# AT89S52.net
KiCad netlist of a schematic drawn in Altium Designer
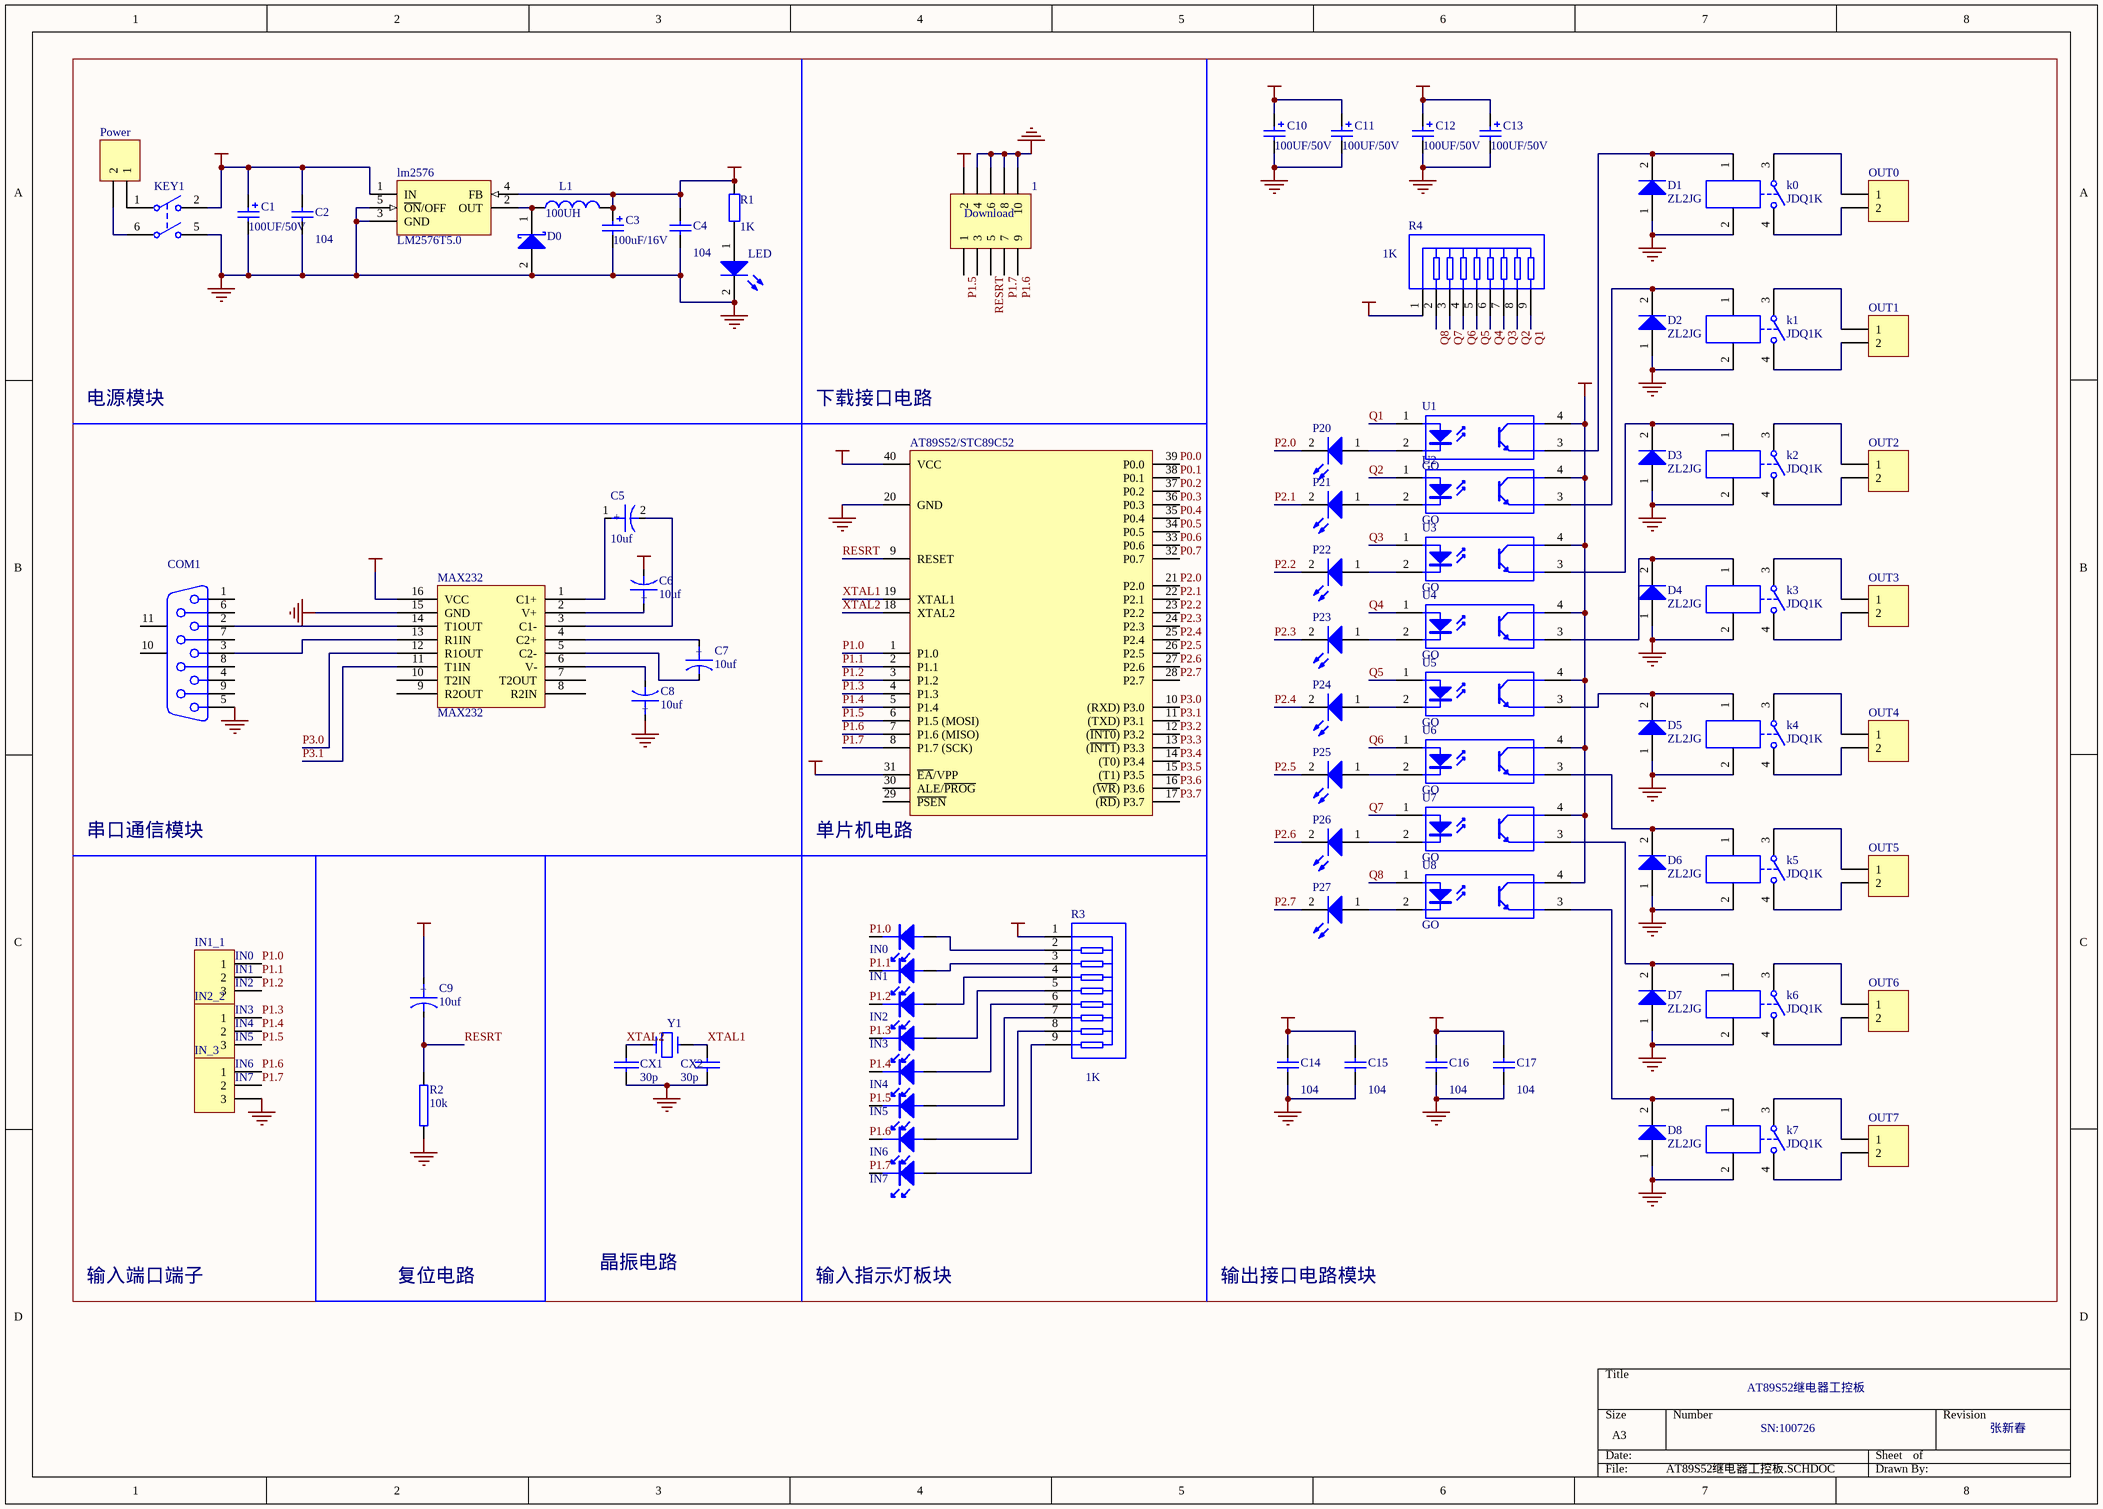
[diagram p0: AT89S52继电器工控板.SCHDOC]

(export (version "E")
  (design (tool "Eeschema 10.0.6"))
  (components
    (comp (ref "1")
      (value "Download")
      (footprint "HDR-2x5")
      (description "Header, 5-Pin, Dual row")
      (fields (field (name "PUBLISHER") "Altium Limited"))
      (libsource (lib "Miscellaneous Connectors") (part "Header 5X2"))
    )
    (comp (ref "AT89S52/STC89C52")
      (value "~")
      (footprint "DIP-40")
      (description "8 位微处理器/40引脚")
      (fields (field (name "发布者") "磊元工作室"))
      (libsource (lib "MCU") (part "AT89S52-P"))
    )
    (comp (ref "C1")
      (value "100UF/50V")
      (footprint "C-DJ-6")
      (description "电解电容")
      (fields (field (name "Comment") "DJDR") (field (name "PUBLISHER") "Altium Limited"))
      (libsource (lib "zxcourhc") (part "DJDR"))
    )
    (comp (ref "C2")
      (value "104")
      (footprint "CPDR")
      (description "瓷片电容")
      (fields (field (name "Comment") "CPDR") (field (name "PUBLISHER") "Altium Limited"))
      (libsource (lib "zxcourhc") (part "CPDR"))
    )
    (comp (ref "C3")
      (value "100uF/16V")
      (footprint "C-DJ-6")
      (description "电解电容")
      (fields (field (name "Comment") "DJDR") (field (name "PUBLISHER") "Altium Limited"))
      (libsource (lib "zxcourhc") (part "DJDR"))
    )
    (comp (ref "C4")
      (value "104")
      (footprint "CPDR")
      (description "瓷片电容")
      (fields (field (name "Comment") "CPDR") (field (name "PUBLISHER") "Altium Limited"))
      (libsource (lib "zxcourhc") (part "CPDR"))
    )
    (comp (ref "C5")
      (value "10uf")
      (footprint "C-DJ-4")
      (description "Capacitor")
      (libsource (lib "") (part "CAPACITOR POL_1"))
    )
    (comp (ref "C6")
      (value "10uf")
      (footprint "C-DJ-4")
      (description "Capacitor")
      (libsource (lib "*") (part "CAPACITOR POL"))
    )
    (comp (ref "C7")
      (value "10uf")
      (footprint "C-DJ-4")
      (description "Capacitor")
      (libsource (lib "*") (part "CAPACITOR POL"))
    )
    (comp (ref "C8")
      (value "10uf")
      (footprint "C-DJ-4")
      (description "Capacitor")
      (libsource (lib "*") (part "CAPACITOR POL"))
    )
    (comp (ref "C9")
      (value "10uf")
      (footprint "C-DJ-4")
      (description "Capacitor")
      (libsource (lib "*") (part "CAPACITOR POL"))
    )
    (comp (ref "C10")
      (value "100UF/50V")
      (footprint "C-DJ-6")
      (description "电解电容")
      (fields (field (name "Comment") "DJDR") (field (name "PUBLISHER") "Altium Limited"))
      (libsource (lib "zxcourhc") (part "DJDR"))
    )
    (comp (ref "C11")
      (value "100UF/50V")
      (footprint "C-DJ-6")
      (description "电解电容")
      (fields (field (name "Comment") "DJDR") (field (name "PUBLISHER") "Altium Limited"))
      (libsource (lib "zxcourhc") (part "DJDR"))
    )
    (comp (ref "C12")
      (value "100UF/50V")
      (footprint "C-DJ-6")
      (description "电解电容")
      (fields (field (name "Comment") "DJDR") (field (name "PUBLISHER") "Altium Limited"))
      (libsource (lib "zxcourhc") (part "DJDR"))
    )
    (comp (ref "C13")
      (value "100UF/50V")
      (footprint "C-DJ-6")
      (description "电解电容")
      (fields (field (name "Comment") "DJDR") (field (name "PUBLISHER") "Altium Limited"))
      (libsource (lib "zxcourhc") (part "DJDR"))
    )
    (comp (ref "C14")
      (value "104")
      (footprint "CPDR")
      (description "瓷片电容")
      (fields (field (name "Comment") "CPDR") (field (name "PUBLISHER") "Altium Limited"))
      (libsource (lib "zxcourhc") (part "CPDR"))
    )
    (comp (ref "C15")
      (value "104")
      (footprint "CPDR")
      (description "瓷片电容")
      (fields (field (name "Comment") "CPDR") (field (name "PUBLISHER") "Altium Limited"))
      (libsource (lib "zxcourhc") (part "CPDR"))
    )
    (comp (ref "C16")
      (value "104")
      (footprint "CPDR")
      (description "瓷片电容")
      (fields (field (name "Comment") "CPDR") (field (name "PUBLISHER") "Altium Limited"))
      (libsource (lib "zxcourhc") (part "CPDR"))
    )
    (comp (ref "C17")
      (value "104")
      (footprint "CPDR")
      (description "瓷片电容")
      (fields (field (name "Comment") "CPDR") (field (name "PUBLISHER") "Altium Limited"))
      (libsource (lib "zxcourhc") (part "CPDR"))
    )
    (comp (ref "COM1")
      (value "D Connector 9")
      (footprint "DSUB1.385-2H9")
      (description "Receptacle Assembly, 9 Position, Right Angle")
      (fields (field (name "PUBLISHER") "Altium Limited"))
      (libsource (lib "Miscellaneous Connectors") (part "D Connector 9"))
    )
    (comp (ref "CX1")
      (value "30p")
      (footprint "HDR1X2")
      (description "Capacitor")
      (libsource (lib "*") (part "CAP"))
    )
    (comp (ref "CX2")
      (value "30p")
      (footprint "HDR1X2")
      (description "Capacitor")
      (libsource (lib "*") (part "CAP"))
    )
    (comp (ref "D0")
      (value "WY2JG")
      (footprint "ZCDZL")
      (description "稳压二级管")
      (fields (field (name "PUBLISHER") "Altium Limited"))
      (libsource (lib "zxcourhc") (part "WY2JG"))
    )
    (comp (ref "D1")
      (value "ZL2JG")
      (footprint "D-ZL-10")
      (description "整流二极管")
      (fields (field (name "PUBLISHER") "Altium Limited"))
      (libsource (lib "zxcourhc") (part "ZL2JG"))
    )
    (comp (ref "D2")
      (value "ZL2JG")
      (footprint "D-ZL-10")
      (description "整流二极管")
      (fields (field (name "PUBLISHER") "Altium Limited"))
      (libsource (lib "zxcourhc") (part "ZL2JG"))
    )
    (comp (ref "D3")
      (value "ZL2JG")
      (footprint "D-ZL-10")
      (description "整流二极管")
      (fields (field (name "PUBLISHER") "Altium Limited"))
      (libsource (lib "zxcourhc") (part "ZL2JG"))
    )
    (comp (ref "D4")
      (value "ZL2JG")
      (footprint "D-ZL-10")
      (description "整流二极管")
      (fields (field (name "PUBLISHER") "Altium Limited"))
      (libsource (lib "zxcourhc") (part "ZL2JG"))
    )
    (comp (ref "D5")
      (value "ZL2JG")
      (footprint "D-ZL-10")
      (description "整流二极管")
      (fields (field (name "PUBLISHER") "Altium Limited"))
      (libsource (lib "zxcourhc") (part "ZL2JG"))
    )
    (comp (ref "D6")
      (value "ZL2JG")
      (footprint "D-ZL-10")
      (description "整流二极管")
      (fields (field (name "PUBLISHER") "Altium Limited"))
      (libsource (lib "zxcourhc") (part "ZL2JG"))
    )
    (comp (ref "D7")
      (value "ZL2JG")
      (footprint "D-ZL-10")
      (description "整流二极管")
      (fields (field (name "PUBLISHER") "Altium Limited"))
      (libsource (lib "zxcourhc") (part "ZL2JG"))
    )
    (comp (ref "D8")
      (value "ZL2JG")
      (footprint "D-ZL-10")
      (description "整流二极管")
      (fields (field (name "PUBLISHER") "Altium Limited"))
      (libsource (lib "zxcourhc") (part "ZL2JG"))
    )
    (comp (ref "IN0") (value "LED") (footprint "HDR1X2") (libsource (lib "OldCow1 (1)") (part "LED")))
    (comp (ref "IN1") (value "LED") (footprint "HDR1X2") (libsource (lib "OldCow1 (1)") (part "LED")))
    (comp (ref "IN1_1")
      (value "PZ_3")
      (footprint "JK128_3")
      (description "排针——3")
      (fields (field (name "PUBLISHER") "Altium Limited"))
      (libsource (lib "zxcourhc") (part "PZ_3"))
    )
    (comp (ref "IN2") (value "LED") (footprint "HDR1X2") (libsource (lib "OldCow1 (1)") (part "LED")))
    (comp (ref "IN2_2")
      (value "PZ_3")
      (footprint "JK128_3")
      (description "排针——3")
      (fields (field (name "PUBLISHER") "Altium Limited"))
      (libsource (lib "zxcourhc") (part "PZ_3"))
    )
    (comp (ref "IN3") (value "LED") (footprint "HDR1X2") (libsource (lib "OldCow1 (1)") (part "LED")))
    (comp (ref "IN4") (value "LED") (footprint "HDR1X2") (libsource (lib "OldCow1 (1)") (part "LED")))
    (comp (ref "IN5") (value "LED") (footprint "HDR1X2") (libsource (lib "OldCow1 (1)") (part "LED")))
    (comp (ref "IN6") (value "LED") (footprint "HDR1X2") (libsource (lib "OldCow1 (1)") (part "LED")))
    (comp (ref "IN7") (value "LED") (footprint "HDR1X2") (libsource (lib "OldCow1 (1)") (part "LED")))
    (comp (ref "IN_3")
      (value "~")
      (footprint "JK128_3")
      (description "排针——3")
      (fields (field (name "PUBLISHER") "Altium Limited"))
      (libsource (lib "zxcourhc") (part "PZ_3"))
    )
    (comp (ref "k0")
      (value "JDQ1K")
      (footprint "JDQ1KI")
      (description "继电器一常开")
      (libsource (lib "zxcourhc") (part "JDQ1K"))
    )
    (comp (ref "k1")
      (value "JDQ1K")
      (footprint "JDQ1KI")
      (description "继电器一常开")
      (libsource (lib "zxcourhc") (part "JDQ1K"))
    )
    (comp (ref "k2")
      (value "JDQ1K")
      (footprint "JDQ1KI")
      (description "继电器一常开")
      (libsource (lib "zxcourhc") (part "JDQ1K"))
    )
    (comp (ref "k3")
      (value "JDQ1K")
      (footprint "JDQ1KI")
      (description "继电器一常开")
      (libsource (lib "zxcourhc") (part "JDQ1K"))
    )
    (comp (ref "k4")
      (value "JDQ1K")
      (footprint "JDQ1KI")
      (description "继电器一常开")
      (libsource (lib "zxcourhc") (part "JDQ1K"))
    )
    (comp (ref "k5")
      (value "JDQ1K")
      (footprint "JDQ1KI")
      (description "继电器一常开")
      (libsource (lib "zxcourhc") (part "JDQ1K"))
    )
    (comp (ref "k6")
      (value "JDQ1K")
      (footprint "JDQ1KI")
      (description "继电器一常开")
      (libsource (lib "zxcourhc") (part "JDQ1K"))
    )
    (comp (ref "k7")
      (value "JDQ1K")
      (footprint "JDQ1KI")
      (description "继电器一常开")
      (libsource (lib "zxcourhc") (part "JDQ1K"))
    )
    (comp (ref "KEY1")
      (value "SW-DPST")
      (footprint "DPDT-6")
      (description "Double-Pole, Single-Throw Switch")
      (fields (field (name "PUBLISHER") "Altium Limited"))
      (libsource (lib "Miscellaneous Devices") (part "SW-DPST"))
    )
    (comp (ref "L1")
      (value "100UH")
      (footprint "L_DG")
      (description "电感")
      (fields (field (name "Comment") "DG") (field (name "PUBLISHER") "Altium Limited"))
      (libsource (lib "zxcourhc") (part "DG"))
    )
    (comp (ref "LED")
      (value "LED")
      (footprint "LED_D")
      (description "发光二极管")
      (fields (field (name "PUBLISHER") "Altium Limited"))
      (libsource (lib "zxcourhc") (part "LED"))
    )
    (comp (ref "lm2576")
      (value "LM2576T5.0")
      (footprint "LM2576")
      (description "Simple Switcher 3A Step Down Voltage Regulator")
      (fields (field (name "PUBLISHER") "Altium Limited"))
      (libsource (lib "NSC Power Mgt Switching Regulator") (part "LM2576HVT-3.3"))
    )
    (comp (ref "MAX232") (value "MAX232") (footprint "DIP16") (libsource (lib "*") (part "MAX232")))
    (comp (ref "OUT0")
      (value "PZ_2")
      (footprint "DYDZ")
      (description "排针——2")
      (fields (field (name "PUBLISHER") "Altium Limited"))
      (libsource (lib "") (part "PZ_2_1"))
    )
    (comp (ref "OUT1")
      (value "PZ_2")
      (footprint "DYDZ")
      (description "排针——2")
      (fields (field (name "PUBLISHER") "Altium Limited"))
      (libsource (lib "") (part "PZ_2_1"))
    )
    (comp (ref "OUT2")
      (value "PZ_2")
      (footprint "DYDZ")
      (description "排针——2")
      (fields (field (name "PUBLISHER") "Altium Limited"))
      (libsource (lib "") (part "PZ_2_1"))
    )
    (comp (ref "OUT3")
      (value "PZ_2")
      (footprint "DYDZ")
      (description "排针——2")
      (fields (field (name "PUBLISHER") "Altium Limited"))
      (libsource (lib "") (part "PZ_2_1"))
    )
    (comp (ref "OUT4")
      (value "PZ_2")
      (footprint "DYDZ")
      (description "排针——2")
      (fields (field (name "PUBLISHER") "Altium Limited"))
      (libsource (lib "") (part "PZ_2_1"))
    )
    (comp (ref "OUT5")
      (value "PZ_2")
      (footprint "DYDZ")
      (description "排针——2")
      (fields (field (name "PUBLISHER") "Altium Limited"))
      (libsource (lib "") (part "PZ_2_1"))
    )
    (comp (ref "OUT6")
      (value "PZ_2")
      (footprint "DYDZ")
      (description "排针——2")
      (fields (field (name "PUBLISHER") "Altium Limited"))
      (libsource (lib "") (part "PZ_2_1"))
    )
    (comp (ref "OUT7")
      (value "PZ_2")
      (footprint "DYDZ")
      (description "排针——2")
      (fields (field (name "PUBLISHER") "Altium Limited"))
      (libsource (lib "") (part "PZ_2_1"))
    )
    (comp (ref "P20")
      (value "~")
      (footprint "CPDR")
      (description "发光二极管")
      (fields (field (name "PUBLISHER") "Altium Limited"))
      (libsource (lib "zxcourhc") (part "LED"))
    )
    (comp (ref "P21")
      (value "~")
      (footprint "CPDR")
      (description "发光二极管")
      (fields (field (name "PUBLISHER") "Altium Limited"))
      (libsource (lib "zxcourhc") (part "LED"))
    )
    (comp (ref "P22")
      (value "~")
      (footprint "CPDR")
      (description "发光二极管")
      (fields (field (name "PUBLISHER") "Altium Limited"))
      (libsource (lib "zxcourhc") (part "LED"))
    )
    (comp (ref "P23")
      (value "~")
      (footprint "CPDR")
      (description "发光二极管")
      (fields (field (name "PUBLISHER") "Altium Limited"))
      (libsource (lib "zxcourhc") (part "LED"))
    )
    (comp (ref "P24")
      (value "~")
      (footprint "CPDR")
      (description "发光二极管")
      (fields (field (name "PUBLISHER") "Altium Limited"))
      (libsource (lib "zxcourhc") (part "LED"))
    )
    (comp (ref "P25")
      (value "~")
      (footprint "CPDR")
      (description "发光二极管")
      (fields (field (name "PUBLISHER") "Altium Limited"))
      (libsource (lib "zxcourhc") (part "LED"))
    )
    (comp (ref "P26")
      (value "~")
      (footprint "CPDR")
      (description "发光二极管")
      (fields (field (name "PUBLISHER") "Altium Limited"))
      (libsource (lib "zxcourhc") (part "LED"))
    )
    (comp (ref "P27")
      (value "~")
      (footprint "CPDR")
      (description "发光二极管")
      (fields (field (name "PUBLISHER") "Altium Limited"))
      (libsource (lib "zxcourhc") (part "LED"))
    )
    (comp (ref "Power")
      (value "PZ_2")
      (footprint "JK128_2")
      (description "排针——2")
      (fields (field (name "PUBLISHER") "Altium Limited"))
      (libsource (lib "zxcourhc") (part "PZ_2"))
    )
    (comp (ref "R1")
      (value "1K")
      (footprint "CPDR")
      (description "电阻")
      (fields (field (name "Comment") "Res") (field (name "PUBLISHER") "Altium Limited"))
      (libsource (lib "zxcourhc") (part "Res"))
    )
    (comp (ref "R2") (value "10k") (footprint "CPDR") (libsource (lib "*") (part "RES2")))
    (comp (ref "R3")
      (value "1K")
      (footprint "HDR-9")
      (description "8位排阻")
      (fields (field (name "PUBLISHER") "Altium Limited"))
      (libsource (lib "zxcourhc") (part "Res PZ_8"))
    )
    (comp (ref "R4")
      (value "1K")
      (footprint "HDR-9")
      (description "8位排阻")
      (fields (field (name "PUBLISHER") "Altium Limited"))
      (libsource (lib "zxcourhc") (part "Res PZ_8"))
    )
    (comp (ref "U1")
      (value "GO")
      (footprint "DIP-4")
      (description "光耦")
      (fields (field (name "PUBLISHER") "Altium Limited"))
      (libsource (lib "zxcourhc") (part "GO"))
    )
    (comp (ref "U2")
      (value "GO")
      (footprint "DIP-4")
      (description "光耦")
      (fields (field (name "PUBLISHER") "Altium Limited"))
      (libsource (lib "zxcourhc") (part "GO"))
    )
    (comp (ref "U3")
      (value "GO")
      (footprint "DIP-4")
      (description "光耦")
      (fields (field (name "PUBLISHER") "Altium Limited"))
      (libsource (lib "zxcourhc") (part "GO"))
    )
    (comp (ref "U4")
      (value "GO")
      (footprint "DIP-4")
      (description "光耦")
      (fields (field (name "PUBLISHER") "Altium Limited"))
      (libsource (lib "zxcourhc") (part "GO"))
    )
    (comp (ref "U5")
      (value "GO")
      (footprint "DIP-4")
      (description "光耦")
      (fields (field (name "PUBLISHER") "Altium Limited"))
      (libsource (lib "zxcourhc") (part "GO"))
    )
    (comp (ref "U6")
      (value "GO")
      (footprint "DIP-4")
      (description "光耦")
      (fields (field (name "PUBLISHER") "Altium Limited"))
      (libsource (lib "zxcourhc") (part "GO"))
    )
    (comp (ref "U7")
      (value "GO")
      (footprint "DIP-4")
      (description "光耦")
      (fields (field (name "PUBLISHER") "Altium Limited"))
      (libsource (lib "zxcourhc") (part "GO"))
    )
    (comp (ref "U8")
      (value "GO")
      (footprint "DIP-4")
      (description "光耦")
      (fields (field (name "PUBLISHER") "Altium Limited"))
      (libsource (lib "zxcourhc") (part "GO"))
    )
    (comp (ref "Y1")
      (value "Y1")
      (footprint "JZ_ZC")
      (description "Crystal")
      (libsource (lib "*") (part "CRYSTAL"))
    )
  )
  (nets
    (net (code "1") (name "+5V") (class "Default")
      (node (ref "1") (pin "2") (pinfunction "2_2") (pintype "passive"))
      (node (ref "AT89S52/STC89C52") (pin "31") (pinfunction "~{EA}/VPP_31") (pintype "passive"))
      (node (ref "AT89S52/STC89C52") (pin "40") (pinfunction "VCC_40") (pintype "power_in"))
      (node (ref "C12") (pin "1") (pinfunction "1_1") (pintype "passive"))
      (node (ref "C13") (pin "1") (pinfunction "1_1") (pintype "passive"))
      (node (ref "C16") (pin "2") (pinfunction "2_2") (pintype "passive"))
      (node (ref "C17") (pin "2") (pinfunction "2_2") (pintype "passive"))
      (node (ref "C3") (pin "1") (pinfunction "1_1") (pintype "passive"))
      (node (ref "C4") (pin "2") (pinfunction "2_2") (pintype "passive"))
      (node (ref "C6") (pin "2") (pinfunction "2_2") (pintype "passive"))
      (node (ref "C9") (pin "1") (pinfunction "1_1") (pintype "passive"))
      (node (ref "L1") (pin "2") (pinfunction "2_2") (pintype "passive"))
      (node (ref "MAX232") (pin "16") (pinfunction "VCC_16") (pintype "passive"))
      (node (ref "R1") (pin "2") (pinfunction "2_2") (pintype "passive"))
      (node (ref "R3") (pin "1") (pinfunction "1_1") (pintype "passive"))
      (node (ref "R4") (pin "1") (pinfunction "1_1") (pintype "passive"))
      (node (ref "lm2576") (pin "4") (pinfunction "FB_4") (pintype "input"))
    )
    (net (code "2") (name "+12V") (class "Default")
      (node (ref "C1") (pin "1") (pinfunction "1_1") (pintype "passive"))
      (node (ref "C10") (pin "1") (pinfunction "1_1") (pintype "passive"))
      (node (ref "C11") (pin "1") (pinfunction "1_1") (pintype "passive"))
      (node (ref "C14") (pin "2") (pinfunction "2_2") (pintype "passive"))
      (node (ref "C15") (pin "2") (pinfunction "2_2") (pintype "passive"))
      (node (ref "C2") (pin "2") (pinfunction "2_2") (pintype "passive"))
      (node (ref "KEY1") (pin "2") (pinfunction "NO1_2") (pintype "passive"))
      (node (ref "U1") (pin "4") (pinfunction "C_4") (pintype "passive"))
      (node (ref "U2") (pin "4") (pinfunction "C_4") (pintype "passive"))
      (node (ref "U3") (pin "4") (pinfunction "C_4") (pintype "passive"))
      (node (ref "U4") (pin "4") (pinfunction "C_4") (pintype "passive"))
      (node (ref "U5") (pin "4") (pinfunction "C_4") (pintype "passive"))
      (node (ref "U6") (pin "4") (pinfunction "C_4") (pintype "passive"))
      (node (ref "U7") (pin "4") (pinfunction "C_4") (pintype "passive"))
      (node (ref "U8") (pin "4") (pinfunction "C_4") (pintype "passive"))
      (node (ref "lm2576") (pin "1") (pinfunction "IN_1") (pintype "power_in"))
    )
    (net (code "3") (name "/P0.0") (class "Default")
      (node (ref "AT89S52/STC89C52") (pin "39") (pinfunction "P0.0_39") (pintype "passive"))
    )
    (net (code "4") (name "/P0.1") (class "Default")
      (node (ref "AT89S52/STC89C52") (pin "38") (pinfunction "P0.1_38") (pintype "passive"))
    )
    (net (code "5") (name "/P0.2") (class "Default")
      (node (ref "AT89S52/STC89C52") (pin "37") (pinfunction "P0.2_37") (pintype "passive"))
    )
    (net (code "6") (name "/P0.3") (class "Default")
      (node (ref "AT89S52/STC89C52") (pin "36") (pinfunction "P0.3_36") (pintype "passive"))
    )
    (net (code "7") (name "/P0.4") (class "Default")
      (node (ref "AT89S52/STC89C52") (pin "35") (pinfunction "P0.4_35") (pintype "passive"))
    )
    (net (code "8") (name "/P0.5") (class "Default")
      (node (ref "AT89S52/STC89C52") (pin "34") (pinfunction "P0.5_34") (pintype "passive"))
    )
    (net (code "9") (name "/P0.6") (class "Default")
      (node (ref "AT89S52/STC89C52") (pin "33") (pinfunction "P0.6_33") (pintype "passive"))
    )
    (net (code "10") (name "/P0.7") (class "Default")
      (node (ref "AT89S52/STC89C52") (pin "32") (pinfunction "P0.7_32") (pintype "passive"))
    )
    (net (code "11") (name "/P1.0") (class "Default")
      (node (ref "AT89S52/STC89C52") (pin "1") (pinfunction "P1.0_1") (pintype "passive"))
      (node (ref "IN0") (pin "2") (pinfunction "K_2") (pintype "passive"))
      (node (ref "IN1_1") (pin "1") (pinfunction "1_1") (pintype "passive"))
    )
    (net (code "12") (name "/P1.1") (class "Default")
      (node (ref "AT89S52/STC89C52") (pin "2") (pinfunction "P1.1_2") (pintype "passive"))
      (node (ref "IN1") (pin "2") (pinfunction "K_2") (pintype "passive"))
      (node (ref "IN1_1") (pin "2") (pinfunction "2_2") (pintype "passive"))
    )
    (net (code "13") (name "/P1.2") (class "Default")
      (node (ref "AT89S52/STC89C52") (pin "3") (pinfunction "P1.2_3") (pintype "passive"))
      (node (ref "IN1_1") (pin "3") (pinfunction "3_3") (pintype "passive"))
      (node (ref "IN2") (pin "2") (pinfunction "K_2") (pintype "passive"))
    )
    (net (code "14") (name "/P1.3") (class "Default")
      (node (ref "AT89S52/STC89C52") (pin "4") (pinfunction "P1.3_4") (pintype "passive"))
      (node (ref "IN2_2") (pin "1") (pinfunction "1_1") (pintype "passive"))
      (node (ref "IN3") (pin "2") (pinfunction "K_2") (pintype "passive"))
    )
    (net (code "15") (name "/P1.4") (class "Default")
      (node (ref "AT89S52/STC89C52") (pin "5") (pinfunction "P1.4_5") (pintype "passive"))
      (node (ref "IN2_2") (pin "2") (pinfunction "2_2") (pintype "passive"))
      (node (ref "IN4") (pin "2") (pinfunction "K_2") (pintype "passive"))
    )
    (net (code "16") (name "/P1.5") (class "Default")
      (node (ref "1") (pin "1") (pinfunction "1_1") (pintype "passive"))
      (node (ref "AT89S52/STC89C52") (pin "6") (pinfunction "P1.5_(MOSI)_6") (pintype "passive"))
      (node (ref "IN2_2") (pin "3") (pinfunction "3_3") (pintype "passive"))
      (node (ref "IN5") (pin "2") (pinfunction "K_2") (pintype "passive"))
    )
    (net (code "17") (name "/P1.6") (class "Default")
      (node (ref "1") (pin "9") (pinfunction "9_9") (pintype "passive"))
      (node (ref "AT89S52/STC89C52") (pin "7") (pinfunction "P1.6_(MISO)_7") (pintype "passive"))
      (node (ref "IN6") (pin "2") (pinfunction "K_2") (pintype "passive"))
      (node (ref "IN_3") (pin "1") (pinfunction "1_1") (pintype "passive"))
    )
    (net (code "18") (name "/P1.7") (class "Default")
      (node (ref "1") (pin "7") (pinfunction "7_7") (pintype "passive"))
      (node (ref "AT89S52/STC89C52") (pin "8") (pinfunction "P1.7_(SCK)_8") (pintype "passive"))
      (node (ref "IN7") (pin "2") (pinfunction "K_2") (pintype "passive"))
      (node (ref "IN_3") (pin "2") (pinfunction "2_2") (pintype "passive"))
    )
    (net (code "19") (name "/P2.0") (class "Default")
      (node (ref "AT89S52/STC89C52") (pin "21") (pinfunction "P2.0_21") (pintype "passive"))
      (node (ref "P20") (pin "2") (pinfunction "K_2") (pintype "passive"))
    )
    (net (code "20") (name "/P2.1") (class "Default")
      (node (ref "AT89S52/STC89C52") (pin "22") (pinfunction "P2.1_22") (pintype "passive"))
      (node (ref "P21") (pin "2") (pinfunction "K_2") (pintype "passive"))
    )
    (net (code "21") (name "/P2.2") (class "Default")
      (node (ref "AT89S52/STC89C52") (pin "23") (pinfunction "P2.2_23") (pintype "passive"))
      (node (ref "P22") (pin "2") (pinfunction "K_2") (pintype "passive"))
    )
    (net (code "22") (name "/P2.3") (class "Default")
      (node (ref "AT89S52/STC89C52") (pin "24") (pinfunction "P2.3_24") (pintype "passive"))
      (node (ref "P23") (pin "2") (pinfunction "K_2") (pintype "passive"))
    )
    (net (code "23") (name "/P2.4") (class "Default")
      (node (ref "AT89S52/STC89C52") (pin "25") (pinfunction "P2.4_25") (pintype "passive"))
      (node (ref "P24") (pin "2") (pinfunction "K_2") (pintype "passive"))
    )
    (net (code "24") (name "/P2.5") (class "Default")
      (node (ref "AT89S52/STC89C52") (pin "26") (pinfunction "P2.5_26") (pintype "passive"))
      (node (ref "P25") (pin "2") (pinfunction "K_2") (pintype "passive"))
    )
    (net (code "25") (name "/P2.6") (class "Default")
      (node (ref "AT89S52/STC89C52") (pin "27") (pinfunction "P2.6_27") (pintype "passive"))
      (node (ref "P26") (pin "2") (pinfunction "K_2") (pintype "passive"))
    )
    (net (code "26") (name "/P2.7") (class "Default")
      (node (ref "AT89S52/STC89C52") (pin "28") (pinfunction "P2.7_28") (pintype "passive"))
      (node (ref "P27") (pin "2") (pinfunction "K_2") (pintype "passive"))
    )
    (net (code "27") (name "/P3.0") (class "Default")
      (node (ref "AT89S52/STC89C52") (pin "10") (pinfunction "(RXD)_P3.0_10") (pintype "passive"))
      (node (ref "MAX232") (pin "12") (pinfunction "R1OUT_12") (pintype "passive"))
    )
    (net (code "28") (name "/P3.1") (class "Default")
      (node (ref "AT89S52/STC89C52") (pin "11") (pinfunction "(TXD)_P3.1_11") (pintype "passive"))
      (node (ref "MAX232") (pin "11") (pinfunction "T1IN_11") (pintype "passive"))
    )
    (net (code "29") (name "/P3.2") (class "Default")
      (node (ref "AT89S52/STC89C52") (pin "12") (pinfunction "(~{INT0})_P3.2_12") (pintype "passive"))
    )
    (net (code "30") (name "/P3.3") (class "Default")
      (node (ref "AT89S52/STC89C52") (pin "13") (pinfunction "(~{INT1})_P3.3_13") (pintype "passive"))
    )
    (net (code "31") (name "/P3.4") (class "Default")
      (node (ref "AT89S52/STC89C52") (pin "14") (pinfunction "(T0)_P3.4_14") (pintype "passive"))
    )
    (net (code "32") (name "/P3.5") (class "Default")
      (node (ref "AT89S52/STC89C52") (pin "15") (pinfunction "(T1)_P3.5_15") (pintype "passive"))
    )
    (net (code "33") (name "/P3.6") (class "Default")
      (node (ref "AT89S52/STC89C52") (pin "16") (pinfunction "(~{WR})_P3.6_16") (pintype "passive"))
    )
    (net (code "34") (name "/P3.7") (class "Default")
      (node (ref "AT89S52/STC89C52") (pin "17") (pinfunction "(~{RD})_P3.7_17") (pintype "passive"))
    )
    (net (code "35") (name "/Q1") (class "Default")
      (node (ref "R4") (pin "9") (pinfunction "9_9") (pintype "passive"))
      (node (ref "U1") (pin "1") (pinfunction "A_1") (pintype "passive"))
    )
    (net (code "36") (name "/Q2") (class "Default")
      (node (ref "R4") (pin "8") (pinfunction "8_8") (pintype "passive"))
      (node (ref "U2") (pin "1") (pinfunction "A_1") (pintype "passive"))
    )
    (net (code "37") (name "/Q3") (class "Default")
      (node (ref "R4") (pin "7") (pinfunction "7_7") (pintype "passive"))
      (node (ref "U3") (pin "1") (pinfunction "A_1") (pintype "passive"))
    )
    (net (code "38") (name "/Q4") (class "Default")
      (node (ref "R4") (pin "6") (pinfunction "6_6") (pintype "passive"))
      (node (ref "U4") (pin "1") (pinfunction "A_1") (pintype "passive"))
    )
    (net (code "39") (name "/Q5") (class "Default")
      (node (ref "R4") (pin "5") (pinfunction "5_5") (pintype "passive"))
      (node (ref "U5") (pin "1") (pinfunction "A_1") (pintype "passive"))
    )
    (net (code "40") (name "/Q6") (class "Default")
      (node (ref "R4") (pin "4") (pinfunction "4_4") (pintype "passive"))
      (node (ref "U6") (pin "1") (pinfunction "A_1") (pintype "passive"))
    )
    (net (code "41") (name "/Q7") (class "Default")
      (node (ref "R4") (pin "3") (pinfunction "3_3") (pintype "passive"))
      (node (ref "U7") (pin "1") (pinfunction "A_1") (pintype "passive"))
    )
    (net (code "42") (name "/Q8") (class "Default")
      (node (ref "R4") (pin "2") (pinfunction "2_2") (pintype "passive"))
      (node (ref "U8") (pin "1") (pinfunction "A_1") (pintype "passive"))
    )
    (net (code "43") (name "/RESRT") (class "Default")
      (node (ref "1") (pin "5") (pinfunction "5_5") (pintype "passive"))
      (node (ref "AT89S52/STC89C52") (pin "9") (pinfunction "RESET_9") (pintype "passive"))
      (node (ref "C9") (pin "2") (pinfunction "2_2") (pintype "passive"))
      (node (ref "R2") (pin "2") (pinfunction "2_2") (pintype "passive"))
    )
    (net (code "44") (name "/XTAL1") (class "Default")
      (node (ref "AT89S52/STC89C52") (pin "19") (pinfunction "XTAL1_19") (pintype "passive"))
      (node (ref "CX2") (pin "1") (pinfunction "1_1") (pintype "passive"))
      (node (ref "Y1") (pin "1") (pinfunction "1_1") (pintype "passive"))
    )
    (net (code "45") (name "/XTAL2") (class "Default")
      (node (ref "AT89S52/STC89C52") (pin "18") (pinfunction "XTAL2_18") (pintype "passive"))
      (node (ref "CX1") (pin "1") (pinfunction "1_1") (pintype "passive"))
      (node (ref "Y1") (pin "2") (pinfunction "2_2") (pintype "passive"))
    )
    (net (code "46") (name "GND") (class "Default")
      (node (ref "1") (pin "10") (pinfunction "10_10") (pintype "passive"))
      (node (ref "1") (pin "4") (pinfunction "4_4") (pintype "passive"))
      (node (ref "1") (pin "6") (pinfunction "6_6") (pintype "passive"))
      (node (ref "1") (pin "8") (pinfunction "8_8") (pintype "passive"))
      (node (ref "AT89S52/STC89C52") (pin "20") (pinfunction "GND_20") (pintype "power_in"))
      (node (ref "C1") (pin "2") (pinfunction "2_2") (pintype "passive"))
      (node (ref "C10") (pin "2") (pinfunction "2_2") (pintype "passive"))
      (node (ref "C11") (pin "2") (pinfunction "2_2") (pintype "passive"))
      (node (ref "C12") (pin "2") (pinfunction "2_2") (pintype "passive"))
      (node (ref "C13") (pin "2") (pinfunction "2_2") (pintype "passive"))
      (node (ref "C14") (pin "1") (pinfunction "1_1") (pintype "passive"))
      (node (ref "C15") (pin "1") (pinfunction "1_1") (pintype "passive"))
      (node (ref "C16") (pin "1") (pinfunction "1_1") (pintype "passive"))
      (node (ref "C17") (pin "1") (pinfunction "1_1") (pintype "passive"))
      (node (ref "C2") (pin "1") (pinfunction "1_1") (pintype "passive"))
      (node (ref "C3") (pin "2") (pinfunction "2_2") (pintype "passive"))
      (node (ref "C4") (pin "1") (pinfunction "1_1") (pintype "passive"))
      (node (ref "C8") (pin "1") (pinfunction "1_1") (pintype "passive"))
      (node (ref "COM1") (pin "5") (pinfunction "5_5") (pintype "passive"))
      (node (ref "CX1") (pin "2") (pinfunction "2_2") (pintype "passive"))
      (node (ref "CX2") (pin "2") (pinfunction "2_2") (pintype "passive"))
      (node (ref "D0") (pin "2") (pinfunction "K_2") (pintype "passive"))
      (node (ref "D1") (pin "1") (pinfunction "A_1") (pintype "passive"))
      (node (ref "D2") (pin "1") (pinfunction "A_1") (pintype "passive"))
      (node (ref "D3") (pin "1") (pinfunction "A_1") (pintype "passive"))
      (node (ref "D4") (pin "1") (pinfunction "A_1") (pintype "passive"))
      (node (ref "D5") (pin "1") (pinfunction "A_1") (pintype "passive"))
      (node (ref "D6") (pin "1") (pinfunction "A_1") (pintype "passive"))
      (node (ref "D7") (pin "1") (pinfunction "A_1") (pintype "passive"))
      (node (ref "D8") (pin "1") (pinfunction "A_1") (pintype "passive"))
      (node (ref "IN_3") (pin "3") (pinfunction "3_3") (pintype "passive"))
      (node (ref "KEY1") (pin "5") (pinfunction "NO2_5") (pintype "passive"))
      (node (ref "LED") (pin "2") (pinfunction "K_2") (pintype "passive"))
      (node (ref "MAX232") (pin "15") (pinfunction "GND_15") (pintype "passive"))
      (node (ref "R2") (pin "1") (pinfunction "1_1") (pintype "passive"))
      (node (ref "k0") (pin "2") (pinfunction "2_2") (pintype "passive"))
      (node (ref "k1") (pin "2") (pinfunction "2_2") (pintype "passive"))
      (node (ref "k2") (pin "2") (pinfunction "2_2") (pintype "passive"))
      (node (ref "k3") (pin "2") (pinfunction "2_2") (pintype "passive"))
      (node (ref "k4") (pin "2") (pinfunction "2_2") (pintype "passive"))
      (node (ref "k5") (pin "2") (pinfunction "2_2") (pintype "passive"))
      (node (ref "k6") (pin "2") (pinfunction "2_2") (pintype "passive"))
      (node (ref "k7") (pin "2") (pinfunction "2_2") (pintype "passive"))
      (node (ref "lm2576") (pin "3") (pinfunction "GND_3") (pintype "power_in"))
      (node (ref "lm2576") (pin "5") (pinfunction "~{ON}/OFF_5") (pintype "input"))
    )
    (net (code "47") (name "Net-(D0-A)") (class "Default")
      (node (ref "D0") (pin "1") (pinfunction "A_1") (pintype "passive"))
      (node (ref "L1") (pin "1") (pinfunction "1_1") (pintype "passive"))
      (node (ref "lm2576") (pin "2") (pinfunction "OUT_2") (pintype "power_in"))
    )
    (net (code "48") (name "Net-(D1-K)") (class "Default")
      (node (ref "D1") (pin "2") (pinfunction "K_2") (pintype "passive"))
      (node (ref "U1") (pin "3") (pinfunction "E_3") (pintype "passive"))
      (node (ref "k0") (pin "1") (pinfunction "1_1") (pintype "passive"))
    )
    (net (code "49") (name "Net-(D2-K)") (class "Default")
      (node (ref "D2") (pin "2") (pinfunction "K_2") (pintype "passive"))
      (node (ref "U2") (pin "3") (pinfunction "E_3") (pintype "passive"))
      (node (ref "k1") (pin "1") (pinfunction "1_1") (pintype "passive"))
    )
    (net (code "50") (name "Net-(D3-K)") (class "Default")
      (node (ref "D3") (pin "2") (pinfunction "K_2") (pintype "passive"))
      (node (ref "U3") (pin "3") (pinfunction "E_3") (pintype "passive"))
      (node (ref "k2") (pin "1") (pinfunction "1_1") (pintype "passive"))
    )
    (net (code "51") (name "Net-(D4-K)") (class "Default")
      (node (ref "D4") (pin "2") (pinfunction "K_2") (pintype "passive"))
      (node (ref "U4") (pin "3") (pinfunction "E_3") (pintype "passive"))
      (node (ref "k3") (pin "1") (pinfunction "1_1") (pintype "passive"))
    )
    (net (code "52") (name "Net-(D5-K)") (class "Default")
      (node (ref "D5") (pin "2") (pinfunction "K_2") (pintype "passive"))
      (node (ref "U5") (pin "3") (pinfunction "E_3") (pintype "passive"))
      (node (ref "k4") (pin "1") (pinfunction "1_1") (pintype "passive"))
    )
    (net (code "53") (name "Net-(D6-K)") (class "Default")
      (node (ref "D6") (pin "2") (pinfunction "K_2") (pintype "passive"))
      (node (ref "U6") (pin "3") (pinfunction "E_3") (pintype "passive"))
      (node (ref "k5") (pin "1") (pinfunction "1_1") (pintype "passive"))
    )
    (net (code "54") (name "Net-(D7-K)") (class "Default")
      (node (ref "D7") (pin "2") (pinfunction "K_2") (pintype "passive"))
      (node (ref "U7") (pin "3") (pinfunction "E_3") (pintype "passive"))
      (node (ref "k6") (pin "1") (pinfunction "1_1") (pintype "passive"))
    )
    (net (code "55") (name "Net-(D8-K)") (class "Default")
      (node (ref "D8") (pin "2") (pinfunction "K_2") (pintype "passive"))
      (node (ref "U8") (pin "3") (pinfunction "E_3") (pintype "passive"))
      (node (ref "k7") (pin "1") (pinfunction "1_1") (pintype "passive"))
    )
    (net (code "56") (name "Net-(IN0-A)") (class "Default")
      (node (ref "IN0") (pin "1") (pinfunction "A_1") (pintype "passive"))
      (node (ref "R3") (pin "2") (pinfunction "2_2") (pintype "passive"))
    )
    (net (code "57") (name "Net-(IN1-A)") (class "Default")
      (node (ref "IN1") (pin "1") (pinfunction "A_1") (pintype "passive"))
      (node (ref "R3") (pin "3") (pinfunction "3_3") (pintype "passive"))
    )
    (net (code "58") (name "Net-(IN2-A)") (class "Default")
      (node (ref "IN2") (pin "1") (pinfunction "A_1") (pintype "passive"))
      (node (ref "R3") (pin "4") (pinfunction "4_4") (pintype "passive"))
    )
    (net (code "59") (name "Net-(IN3-A)") (class "Default")
      (node (ref "IN3") (pin "1") (pinfunction "A_1") (pintype "passive"))
      (node (ref "R3") (pin "5") (pinfunction "5_5") (pintype "passive"))
    )
    (net (code "60") (name "Net-(IN4-A)") (class "Default")
      (node (ref "IN4") (pin "1") (pinfunction "A_1") (pintype "passive"))
      (node (ref "R3") (pin "6") (pinfunction "6_6") (pintype "passive"))
    )
    (net (code "61") (name "Net-(IN5-A)") (class "Default")
      (node (ref "IN5") (pin "1") (pinfunction "A_1") (pintype "passive"))
      (node (ref "R3") (pin "7") (pinfunction "7_7") (pintype "passive"))
    )
    (net (code "62") (name "Net-(IN6-A)") (class "Default")
      (node (ref "IN6") (pin "1") (pinfunction "A_1") (pintype "passive"))
      (node (ref "R3") (pin "8") (pinfunction "8_8") (pintype "passive"))
    )
    (net (code "63") (name "Net-(IN7-A)") (class "Default")
      (node (ref "IN7") (pin "1") (pinfunction "A_1") (pintype "passive"))
      (node (ref "R3") (pin "9") (pinfunction "9_9") (pintype "passive"))
    )
    (net (code "64") (name "Net-(KEY1-COMMON1)") (class "Default")
      (node (ref "KEY1") (pin "1") (pinfunction "COMMON1_1") (pintype "passive"))
      (node (ref "Power") (pin "1") (pinfunction "1_1") (pintype "passive"))
    )
    (net (code "65") (name "Net-(KEY1-COMMON2)") (class "Default")
      (node (ref "KEY1") (pin "6") (pinfunction "COMMON2_6") (pintype "passive"))
      (node (ref "Power") (pin "2") (pinfunction "2_2") (pintype "passive"))
    )
    (net (code "66") (name "Net-(LED-A)") (class "Default")
      (node (ref "LED") (pin "1") (pinfunction "A_1") (pintype "passive"))
      (node (ref "R1") (pin "1") (pinfunction "1_1") (pintype "passive"))
    )
    (net (code "67") (name "Net-(MAX232-C1+)") (class "Default")
      (node (ref "C5") (pin "1") (pinfunction "1_1") (pintype "passive"))
      (node (ref "MAX232") (pin "1") (pinfunction "C1+_1") (pintype "passive"))
    )
    (net (code "68") (name "Net-(MAX232-C1-)") (class "Default")
      (node (ref "C5") (pin "2") (pinfunction "2_2") (pintype "passive"))
      (node (ref "MAX232") (pin "3") (pinfunction "C1-_3") (pintype "passive"))
    )
    (net (code "69") (name "Net-(MAX232-C2+)") (class "Default")
      (node (ref "C7") (pin "1") (pinfunction "1_1") (pintype "passive"))
      (node (ref "MAX232") (pin "4") (pinfunction "C2+_4") (pintype "passive"))
    )
    (net (code "70") (name "Net-(MAX232-C2-)") (class "Default")
      (node (ref "C7") (pin "2") (pinfunction "2_2") (pintype "passive"))
      (node (ref "MAX232") (pin "5") (pinfunction "C2-_5") (pintype "passive"))
    )
    (net (code "71") (name "Net-(MAX232-R1IN)") (class "Default")
      (node (ref "COM1") (pin "3") (pinfunction "3_3") (pintype "passive"))
      (node (ref "MAX232") (pin "13") (pinfunction "R1IN_13") (pintype "passive"))
    )
    (net (code "72") (name "Net-(MAX232-T1OUT)") (class "Default")
      (node (ref "COM1") (pin "2") (pinfunction "2_2") (pintype "passive"))
      (node (ref "MAX232") (pin "14") (pinfunction "T1OUT_14") (pintype "passive"))
    )
    (net (code "73") (name "Net-(MAX232-V+)") (class "Default")
      (node (ref "C6") (pin "1") (pinfunction "1_1") (pintype "passive"))
      (node (ref "MAX232") (pin "2") (pinfunction "V+_2") (pintype "passive"))
    )
    (net (code "74") (name "Net-(MAX232-V-)") (class "Default")
      (node (ref "C8") (pin "2") (pinfunction "2_2") (pintype "passive"))
      (node (ref "MAX232") (pin "6") (pinfunction "V-_6") (pintype "passive"))
    )
    (net (code "75") (name "Net-(OUT0-Pad1)") (class "Default")
      (node (ref "OUT0") (pin "1") (pinfunction "1_1") (pintype "passive"))
      (node (ref "k0") (pin "3") (pinfunction "3_3") (pintype "passive"))
    )
    (net (code "76") (name "Net-(OUT0-Pad2)") (class "Default")
      (node (ref "OUT0") (pin "2") (pinfunction "2_2") (pintype "passive"))
      (node (ref "k0") (pin "4") (pinfunction "4_4") (pintype "passive"))
    )
    (net (code "77") (name "Net-(OUT1-Pad1)") (class "Default")
      (node (ref "OUT1") (pin "1") (pinfunction "1_1") (pintype "passive"))
      (node (ref "k1") (pin "3") (pinfunction "3_3") (pintype "passive"))
    )
    (net (code "78") (name "Net-(OUT1-Pad2)") (class "Default")
      (node (ref "OUT1") (pin "2") (pinfunction "2_2") (pintype "passive"))
      (node (ref "k1") (pin "4") (pinfunction "4_4") (pintype "passive"))
    )
    (net (code "79") (name "Net-(OUT2-Pad1)") (class "Default")
      (node (ref "OUT2") (pin "1") (pinfunction "1_1") (pintype "passive"))
      (node (ref "k2") (pin "3") (pinfunction "3_3") (pintype "passive"))
    )
    (net (code "80") (name "Net-(OUT2-Pad2)") (class "Default")
      (node (ref "OUT2") (pin "2") (pinfunction "2_2") (pintype "passive"))
      (node (ref "k2") (pin "4") (pinfunction "4_4") (pintype "passive"))
    )
    (net (code "81") (name "Net-(OUT3-Pad1)") (class "Default")
      (node (ref "OUT3") (pin "1") (pinfunction "1_1") (pintype "passive"))
      (node (ref "k3") (pin "3") (pinfunction "3_3") (pintype "passive"))
    )
    (net (code "82") (name "Net-(OUT3-Pad2)") (class "Default")
      (node (ref "OUT3") (pin "2") (pinfunction "2_2") (pintype "passive"))
      (node (ref "k3") (pin "4") (pinfunction "4_4") (pintype "passive"))
    )
    (net (code "83") (name "Net-(OUT4-Pad1)") (class "Default")
      (node (ref "OUT4") (pin "1") (pinfunction "1_1") (pintype "passive"))
      (node (ref "k4") (pin "3") (pinfunction "3_3") (pintype "passive"))
    )
    (net (code "84") (name "Net-(OUT4-Pad2)") (class "Default")
      (node (ref "OUT4") (pin "2") (pinfunction "2_2") (pintype "passive"))
      (node (ref "k4") (pin "4") (pinfunction "4_4") (pintype "passive"))
    )
    (net (code "85") (name "Net-(OUT5-Pad1)") (class "Default")
      (node (ref "OUT5") (pin "1") (pinfunction "1_1") (pintype "passive"))
      (node (ref "k5") (pin "3") (pinfunction "3_3") (pintype "passive"))
    )
    (net (code "86") (name "Net-(OUT5-Pad2)") (class "Default")
      (node (ref "OUT5") (pin "2") (pinfunction "2_2") (pintype "passive"))
      (node (ref "k5") (pin "4") (pinfunction "4_4") (pintype "passive"))
    )
    (net (code "87") (name "Net-(OUT6-Pad1)") (class "Default")
      (node (ref "OUT6") (pin "1") (pinfunction "1_1") (pintype "passive"))
      (node (ref "k6") (pin "3") (pinfunction "3_3") (pintype "passive"))
    )
    (net (code "88") (name "Net-(OUT6-Pad2)") (class "Default")
      (node (ref "OUT6") (pin "2") (pinfunction "2_2") (pintype "passive"))
      (node (ref "k6") (pin "4") (pinfunction "4_4") (pintype "passive"))
    )
    (net (code "89") (name "Net-(OUT7-Pad1)") (class "Default")
      (node (ref "OUT7") (pin "1") (pinfunction "1_1") (pintype "passive"))
      (node (ref "k7") (pin "3") (pinfunction "3_3") (pintype "passive"))
    )
    (net (code "90") (name "Net-(OUT7-Pad2)") (class "Default")
      (node (ref "OUT7") (pin "2") (pinfunction "2_2") (pintype "passive"))
      (node (ref "k7") (pin "4") (pinfunction "4_4") (pintype "passive"))
    )
    (net (code "91") (name "Net-(P20-A)") (class "Default")
      (node (ref "P20") (pin "1") (pinfunction "A_1") (pintype "passive"))
      (node (ref "U1") (pin "2") (pinfunction "K_2") (pintype "passive"))
    )
    (net (code "92") (name "Net-(P21-A)") (class "Default")
      (node (ref "P21") (pin "1") (pinfunction "A_1") (pintype "passive"))
      (node (ref "U2") (pin "2") (pinfunction "K_2") (pintype "passive"))
    )
    (net (code "93") (name "Net-(P22-A)") (class "Default")
      (node (ref "P22") (pin "1") (pinfunction "A_1") (pintype "passive"))
      (node (ref "U3") (pin "2") (pinfunction "K_2") (pintype "passive"))
    )
    (net (code "94") (name "Net-(P23-A)") (class "Default")
      (node (ref "P23") (pin "1") (pinfunction "A_1") (pintype "passive"))
      (node (ref "U4") (pin "2") (pinfunction "K_2") (pintype "passive"))
    )
    (net (code "95") (name "Net-(P24-A)") (class "Default")
      (node (ref "P24") (pin "1") (pinfunction "A_1") (pintype "passive"))
      (node (ref "U5") (pin "2") (pinfunction "K_2") (pintype "passive"))
    )
    (net (code "96") (name "Net-(P25-A)") (class "Default")
      (node (ref "P25") (pin "1") (pinfunction "A_1") (pintype "passive"))
      (node (ref "U6") (pin "2") (pinfunction "K_2") (pintype "passive"))
    )
    (net (code "97") (name "Net-(P26-A)") (class "Default")
      (node (ref "P26") (pin "1") (pinfunction "A_1") (pintype "passive"))
      (node (ref "U7") (pin "2") (pinfunction "K_2") (pintype "passive"))
    )
    (net (code "98") (name "Net-(P27-A)") (class "Default")
      (node (ref "P27") (pin "1") (pinfunction "A_1") (pintype "passive"))
      (node (ref "U8") (pin "2") (pinfunction "K_2") (pintype "passive"))
    )
    (net (code "99") (name "unconnected-(1-Pad3)") (class "Default")
      (node (ref "1") (pin "3") (pinfunction "3_3") (pintype "passive"))
    )
    (net (code "100") (name "unconnected-(AT89S52/STC89C52-ALE{slash}~{PROG}-Pad30)") (class "Default")
      (node (ref "AT89S52/STC89C52") (pin "30") (pinfunction "ALE/~{PROG}_30") (pintype "passive"))
    )
    (net (code "101") (name "unconnected-(AT89S52/STC89C52-~{PSEN}-Pad29)") (class "Default")
      (node (ref "AT89S52/STC89C52") (pin "29") (pinfunction "~{PSEN}_29") (pintype "passive"))
    )
    (net (code "102") (name "unconnected-(COM1-MH1-Pad10)") (class "Default")
      (node (ref "COM1") (pin "10") (pinfunction "MH1_10") (pintype "passive"))
    )
    (net (code "103") (name "unconnected-(COM1-MH2-Pad11)") (class "Default")
      (node (ref "COM1") (pin "11") (pinfunction "MH2_11") (pintype "passive"))
    )
    (net (code "104") (name "unconnected-(COM1-Pad1)") (class "Default")
      (node (ref "COM1") (pin "1") (pinfunction "1_1") (pintype "passive"))
    )
    (net (code "105") (name "unconnected-(COM1-Pad4)") (class "Default")
      (node (ref "COM1") (pin "4") (pinfunction "4_4") (pintype "passive"))
    )
    (net (code "106") (name "unconnected-(COM1-Pad6)") (class "Default")
      (node (ref "COM1") (pin "6") (pinfunction "6_6") (pintype "passive"))
    )
    (net (code "107") (name "unconnected-(COM1-Pad7)") (class "Default")
      (node (ref "COM1") (pin "7") (pinfunction "7_7") (pintype "passive"))
    )
    (net (code "108") (name "unconnected-(COM1-Pad8)") (class "Default")
      (node (ref "COM1") (pin "8") (pinfunction "8_8") (pintype "passive"))
    )
    (net (code "109") (name "unconnected-(COM1-Pad9)") (class "Default")
      (node (ref "COM1") (pin "9") (pinfunction "9_9") (pintype "passive"))
    )
    (net (code "110") (name "unconnected-(MAX232-R2IN-Pad8)") (class "Default")
      (node (ref "MAX232") (pin "8") (pinfunction "R2IN_8") (pintype "passive"))
    )
    (net (code "111") (name "unconnected-(MAX232-R2OUT-Pad9)") (class "Default")
      (node (ref "MAX232") (pin "9") (pinfunction "R2OUT_9") (pintype "passive"))
    )
    (net (code "112") (name "unconnected-(MAX232-T2IN-Pad10)") (class "Default")
      (node (ref "MAX232") (pin "10") (pinfunction "T2IN_10") (pintype "passive"))
    )
    (net (code "113") (name "unconnected-(MAX232-T2OUT-Pad7)") (class "Default")
      (node (ref "MAX232") (pin "7") (pinfunction "T2OUT_7") (pintype "passive"))
    )
  )
)
